# fpga-bank7-outside.net
KiCad netlist of a schematic drawn in Altium Designer
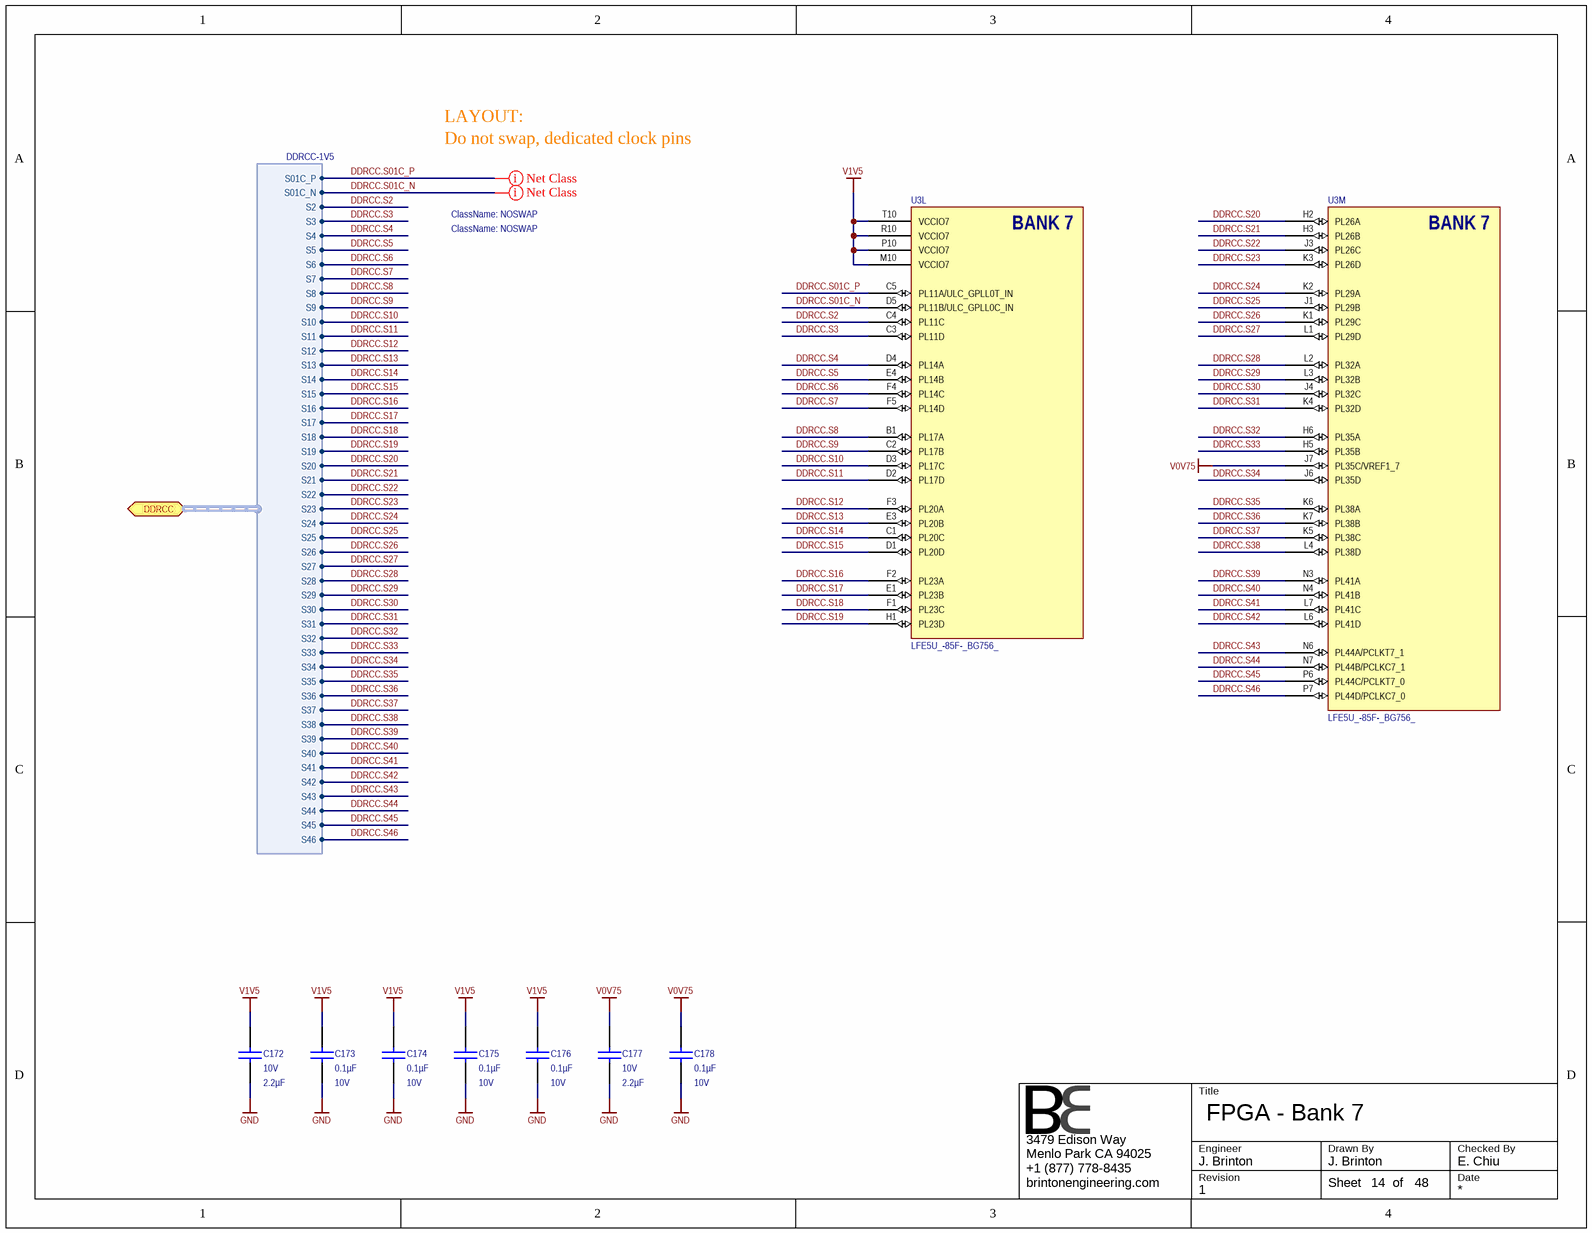
[diagram p0: fpga-bank7-outside.SchDoc]

(export (version "E")
  (design (tool "Eeschema 10.0.6"))
  (components
    (comp (ref "C172")
      (value "GRM188R71A225KE15D")
      (footprint "CAPC1608X90N")
      (description "CAP CER 2.2UF 10V 10% X7R 0603")
      (fields
        (field (name "MANUFACTURER") "Murata Electronics North America")
        (field (name "TOLERANCE") "±10%")
        (field (name "VOLTAGE - RATED") "10V")
        (field (name "CAPACITANCE") "2.2µF")
      )
      (libsource (lib "murata") (part "GRM188R71A225KE15D"))
    )
    (comp (ref "C173")
      (value "GRM155R71A104KA01J")
      (footprint "CAPC1005X56N")
      (description "CAP CER 0.1UF 10V 10% X7R 0402")
      (fields
        (field (name "MANUFACTURER") "Murata Electronics North America")
        (field (name "TOLERANCE") "±10%")
        (field (name "CAPACITANCE") "0.1µF")
        (field (name "VOLTAGE - RATED") "10V")
      )
      (libsource (lib "murata") (part "GRM155R71A104KA01J"))
    )
    (comp (ref "C174")
      (value "GRM155R71A104KA01J")
      (footprint "CAPC1005X56N")
      (description "CAP CER 0.1UF 10V 10% X7R 0402")
      (fields
        (field (name "MANUFACTURER") "Murata Electronics North America")
        (field (name "TOLERANCE") "±10%")
        (field (name "CAPACITANCE") "0.1µF")
        (field (name "VOLTAGE - RATED") "10V")
      )
      (libsource (lib "murata") (part "GRM155R71A104KA01J"))
    )
    (comp (ref "C175")
      (value "GRM155R71A104KA01J")
      (footprint "CAPC1005X56N")
      (description "CAP CER 0.1UF 10V 10% X7R 0402")
      (fields
        (field (name "MANUFACTURER") "Murata Electronics North America")
        (field (name "TOLERANCE") "±10%")
        (field (name "CAPACITANCE") "0.1µF")
        (field (name "VOLTAGE - RATED") "10V")
      )
      (libsource (lib "murata") (part "GRM155R71A104KA01J"))
    )
    (comp (ref "C176")
      (value "GRM155R71A104KA01J")
      (footprint "CAPC1005X56N")
      (description "CAP CER 0.1UF 10V 10% X7R 0402")
      (fields
        (field (name "MANUFACTURER") "Murata Electronics North America")
        (field (name "TOLERANCE") "±10%")
        (field (name "CAPACITANCE") "0.1µF")
        (field (name "VOLTAGE - RATED") "10V")
      )
      (libsource (lib "murata") (part "GRM155R71A104KA01J"))
    )
    (comp (ref "C177")
      (value "GRM188R71A225KE15D")
      (footprint "CAPC1608X90N")
      (description "CAP CER 2.2UF 10V 10% X7R 0603")
      (fields
        (field (name "MANUFACTURER") "Murata Electronics North America")
        (field (name "TOLERANCE") "±10%")
        (field (name "VOLTAGE - RATED") "10V")
        (field (name "CAPACITANCE") "2.2µF")
      )
      (libsource (lib "murata") (part "GRM188R71A225KE15D"))
    )
    (comp (ref "C178")
      (value "GRM155R71A104KA01J")
      (footprint "CAPC1005X56N")
      (description "CAP CER 0.1UF 10V 10% X7R 0402")
      (fields
        (field (name "MANUFACTURER") "Murata Electronics North America")
        (field (name "TOLERANCE") "±10%")
        (field (name "CAPACITANCE") "0.1µF")
        (field (name "VOLTAGE - RATED") "10V")
      )
      (libsource (lib "murata") (part "GRM155R71A104KA01J"))
    )
    (comp (ref "U3")
      (value "LFE5U_-85F-_BG756_")
      (footprint "lattice:caBGA756")
      (description "ECP5 FPGA, 85k LUT, 756-caBGA")
      (fields (field (name "MANUFACTURER") "Lattice Semiconductor"))
      (libsource (lib "lattice") (part "LFE5U_-85F-_BG756_"))
    )
  )
  (nets
    (net (code "2") (name "/DDRCC.S01C_N") (class "Default")
      (node (ref "U3") (pin "D5") (pinfunction "PL11B/ULC_GPLL0C_IN_D5") (pintype "bidirectional"))
    )
    (net (code "3") (name "/DDRCC.S01C_P") (class "Default")
      (node (ref "U3") (pin "C5") (pinfunction "PL11A/ULC_GPLL0T_IN_C5") (pintype "bidirectional"))
    )
    (net (code "4") (name "/DDRCC.S2") (class "Default")
      (node (ref "U3") (pin "C4") (pinfunction "PL11C_C4") (pintype "bidirectional"))
    )
    (net (code "5") (name "/DDRCC.S3") (class "Default")
      (node (ref "U3") (pin "C3") (pinfunction "PL11D_C3") (pintype "bidirectional"))
    )
    (net (code "6") (name "/DDRCC.S4") (class "Default")
      (node (ref "U3") (pin "D4") (pinfunction "PL14A_D4") (pintype "bidirectional"))
    )
    (net (code "7") (name "/DDRCC.S5") (class "Default")
      (node (ref "U3") (pin "E4") (pinfunction "PL14B_E4") (pintype "bidirectional"))
    )
    (net (code "8") (name "/DDRCC.S6") (class "Default")
      (node (ref "U3") (pin "F4") (pinfunction "PL14C_F4") (pintype "bidirectional"))
    )
    (net (code "9") (name "/DDRCC.S7") (class "Default")
      (node (ref "U3") (pin "F5") (pinfunction "PL14D_F5") (pintype "bidirectional"))
    )
    (net (code "10") (name "/DDRCC.S8") (class "Default")
      (node (ref "U3") (pin "B1") (pinfunction "PL17A_B1") (pintype "bidirectional"))
    )
    (net (code "11") (name "/DDRCC.S9") (class "Default")
      (node (ref "U3") (pin "C2") (pinfunction "PL17B_C2") (pintype "bidirectional"))
    )
    (net (code "12") (name "/DDRCC.S10") (class "Default")
      (node (ref "U3") (pin "D3") (pinfunction "PL17C_D3") (pintype "bidirectional"))
    )
    (net (code "13") (name "/DDRCC.S11") (class "Default")
      (node (ref "U3") (pin "D2") (pinfunction "PL17D_D2") (pintype "bidirectional"))
    )
    (net (code "14") (name "/DDRCC.S12") (class "Default")
      (node (ref "U3") (pin "F3") (pinfunction "PL20A_F3") (pintype "bidirectional"))
    )
    (net (code "15") (name "/DDRCC.S13") (class "Default")
      (node (ref "U3") (pin "E3") (pinfunction "PL20B_E3") (pintype "bidirectional"))
    )
    (net (code "16") (name "/DDRCC.S14") (class "Default")
      (node (ref "U3") (pin "C1") (pinfunction "PL20C_C1") (pintype "bidirectional"))
    )
    (net (code "17") (name "/DDRCC.S15") (class "Default")
      (node (ref "U3") (pin "D1") (pinfunction "PL20D_D1") (pintype "bidirectional"))
    )
    (net (code "18") (name "/DDRCC.S16") (class "Default")
      (node (ref "U3") (pin "F2") (pinfunction "PL23A_F2") (pintype "bidirectional"))
    )
    (net (code "19") (name "/DDRCC.S17") (class "Default")
      (node (ref "U3") (pin "E1") (pinfunction "PL23B_E1") (pintype "bidirectional"))
    )
    (net (code "20") (name "/DDRCC.S18") (class "Default")
      (node (ref "U3") (pin "F1") (pinfunction "PL23C_F1") (pintype "bidirectional"))
    )
    (net (code "21") (name "/DDRCC.S19") (class "Default")
      (node (ref "U3") (pin "H1") (pinfunction "PL23D_H1") (pintype "bidirectional"))
    )
    (net (code "22") (name "/DDRCC.S20") (class "Default")
      (node (ref "U3") (pin "H2") (pinfunction "PL26A_H2") (pintype "bidirectional"))
    )
    (net (code "23") (name "/DDRCC.S21") (class "Default")
      (node (ref "U3") (pin "H3") (pinfunction "PL26B_H3") (pintype "bidirectional"))
    )
    (net (code "24") (name "/DDRCC.S22") (class "Default")
      (node (ref "U3") (pin "J3") (pinfunction "PL26C_J3") (pintype "bidirectional"))
    )
    (net (code "25") (name "/DDRCC.S23") (class "Default")
      (node (ref "U3") (pin "K3") (pinfunction "PL26D_K3") (pintype "bidirectional"))
    )
    (net (code "26") (name "/DDRCC.S24") (class "Default")
      (node (ref "U3") (pin "K2") (pinfunction "PL29A_K2") (pintype "bidirectional"))
    )
    (net (code "27") (name "/DDRCC.S25") (class "Default")
      (node (ref "U3") (pin "J1") (pinfunction "PL29B_J1") (pintype "bidirectional"))
    )
    (net (code "28") (name "/DDRCC.S26") (class "Default")
      (node (ref "U3") (pin "K1") (pinfunction "PL29C_K1") (pintype "bidirectional"))
    )
    (net (code "29") (name "/DDRCC.S27") (class "Default")
      (node (ref "U3") (pin "L1") (pinfunction "PL29D_L1") (pintype "bidirectional"))
    )
    (net (code "30") (name "/DDRCC.S28") (class "Default")
      (node (ref "U3") (pin "L2") (pinfunction "PL32A_L2") (pintype "bidirectional"))
    )
    (net (code "31") (name "/DDRCC.S29") (class "Default")
      (node (ref "U3") (pin "L3") (pinfunction "PL32B_L3") (pintype "bidirectional"))
    )
    (net (code "32") (name "/DDRCC.S30") (class "Default")
      (node (ref "U3") (pin "J4") (pinfunction "PL32C_J4") (pintype "bidirectional"))
    )
    (net (code "33") (name "/DDRCC.S31") (class "Default")
      (node (ref "U3") (pin "K4") (pinfunction "PL32D_K4") (pintype "bidirectional"))
    )
    (net (code "34") (name "/DDRCC.S32") (class "Default")
      (node (ref "U3") (pin "H6") (pinfunction "PL35A_H6") (pintype "bidirectional"))
    )
    (net (code "35") (name "/DDRCC.S33") (class "Default")
      (node (ref "U3") (pin "H5") (pinfunction "PL35B_H5") (pintype "bidirectional"))
    )
    (net (code "36") (name "/DDRCC.S34") (class "Default")
      (node (ref "U3") (pin "J6") (pinfunction "PL35D_J6") (pintype "bidirectional"))
    )
    (net (code "37") (name "/DDRCC.S35") (class "Default")
      (node (ref "U3") (pin "K6") (pinfunction "PL38A_K6") (pintype "bidirectional"))
    )
    (net (code "38") (name "/DDRCC.S36") (class "Default")
      (node (ref "U3") (pin "K7") (pinfunction "PL38B_K7") (pintype "bidirectional"))
    )
    (net (code "39") (name "/DDRCC.S37") (class "Default")
      (node (ref "U3") (pin "K5") (pinfunction "PL38C_K5") (pintype "bidirectional"))
    )
    (net (code "40") (name "/DDRCC.S38") (class "Default")
      (node (ref "U3") (pin "L4") (pinfunction "PL38D_L4") (pintype "bidirectional"))
    )
    (net (code "41") (name "/DDRCC.S39") (class "Default")
      (node (ref "U3") (pin "N3") (pinfunction "PL41A_N3") (pintype "bidirectional"))
    )
    (net (code "42") (name "/DDRCC.S40") (class "Default")
      (node (ref "U3") (pin "N4") (pinfunction "PL41B_N4") (pintype "bidirectional"))
    )
    (net (code "43") (name "/DDRCC.S41") (class "Default")
      (node (ref "U3") (pin "L7") (pinfunction "PL41C_L7") (pintype "bidirectional"))
    )
    (net (code "44") (name "/DDRCC.S42") (class "Default")
      (node (ref "U3") (pin "L6") (pinfunction "PL41D_L6") (pintype "bidirectional"))
    )
    (net (code "45") (name "/DDRCC.S43") (class "Default")
      (node (ref "U3") (pin "N6") (pinfunction "PL44A/PCLKT7_1_N6") (pintype "bidirectional"))
    )
    (net (code "46") (name "/DDRCC.S44") (class "Default")
      (node (ref "U3") (pin "N7") (pinfunction "PL44B/PCLKC7_1_N7") (pintype "bidirectional"))
    )
    (net (code "47") (name "/DDRCC.S45") (class "Default")
      (node (ref "U3") (pin "P6") (pinfunction "PL44C/PCLKT7_0_P6") (pintype "bidirectional"))
    )
    (net (code "48") (name "/DDRCC.S46") (class "Default")
      (node (ref "U3") (pin "P7") (pinfunction "PL44D/PCLKC7_0_P7") (pintype "bidirectional"))
    )
    (net (code "50") (name "GND") (class "Default")
      (node (ref "C172") (pin "1") (pinfunction "1_1") (pintype "passive"))
      (node (ref "C173") (pin "1") (pinfunction "1_1") (pintype "passive"))
      (node (ref "C174") (pin "1") (pinfunction "1_1") (pintype "passive"))
      (node (ref "C175") (pin "1") (pinfunction "1_1") (pintype "passive"))
      (node (ref "C176") (pin "1") (pinfunction "1_1") (pintype "passive"))
      (node (ref "C177") (pin "1") (pinfunction "1_1") (pintype "passive"))
      (node (ref "C178") (pin "1") (pinfunction "1_1") (pintype "passive"))
    )
    (net (code "51") (name "V0V75") (class "Default")
      (node (ref "C177") (pin "2") (pinfunction "2_2") (pintype "passive"))
      (node (ref "C178") (pin "2") (pinfunction "2_2") (pintype "passive"))
      (node (ref "U3") (pin "J7") (pinfunction "PL35C/VREF1_7_J7") (pintype "bidirectional"))
    )
    (net (code "52") (name "V1V5") (class "Default")
      (node (ref "C172") (pin "2") (pinfunction "2_2") (pintype "passive"))
      (node (ref "C173") (pin "2") (pinfunction "2_2") (pintype "passive"))
      (node (ref "C174") (pin "2") (pinfunction "2_2") (pintype "passive"))
      (node (ref "C175") (pin "2") (pinfunction "2_2") (pintype "passive"))
      (node (ref "C176") (pin "2") (pinfunction "2_2") (pintype "passive"))
      (node (ref "U3") (pin "M10") (pinfunction "VCCIO7_M10") (pintype "power_in"))
      (node (ref "U3") (pin "P10") (pinfunction "VCCIO7_P10") (pintype "power_in"))
      (node (ref "U3") (pin "R10") (pinfunction "VCCIO7_R10") (pintype "power_in"))
      (node (ref "U3") (pin "T10") (pinfunction "VCCIO7_T10") (pintype "power_in"))
    )
  )
)
